# M652X.net
KiCad netlist of a schematic drawn in EAGLE
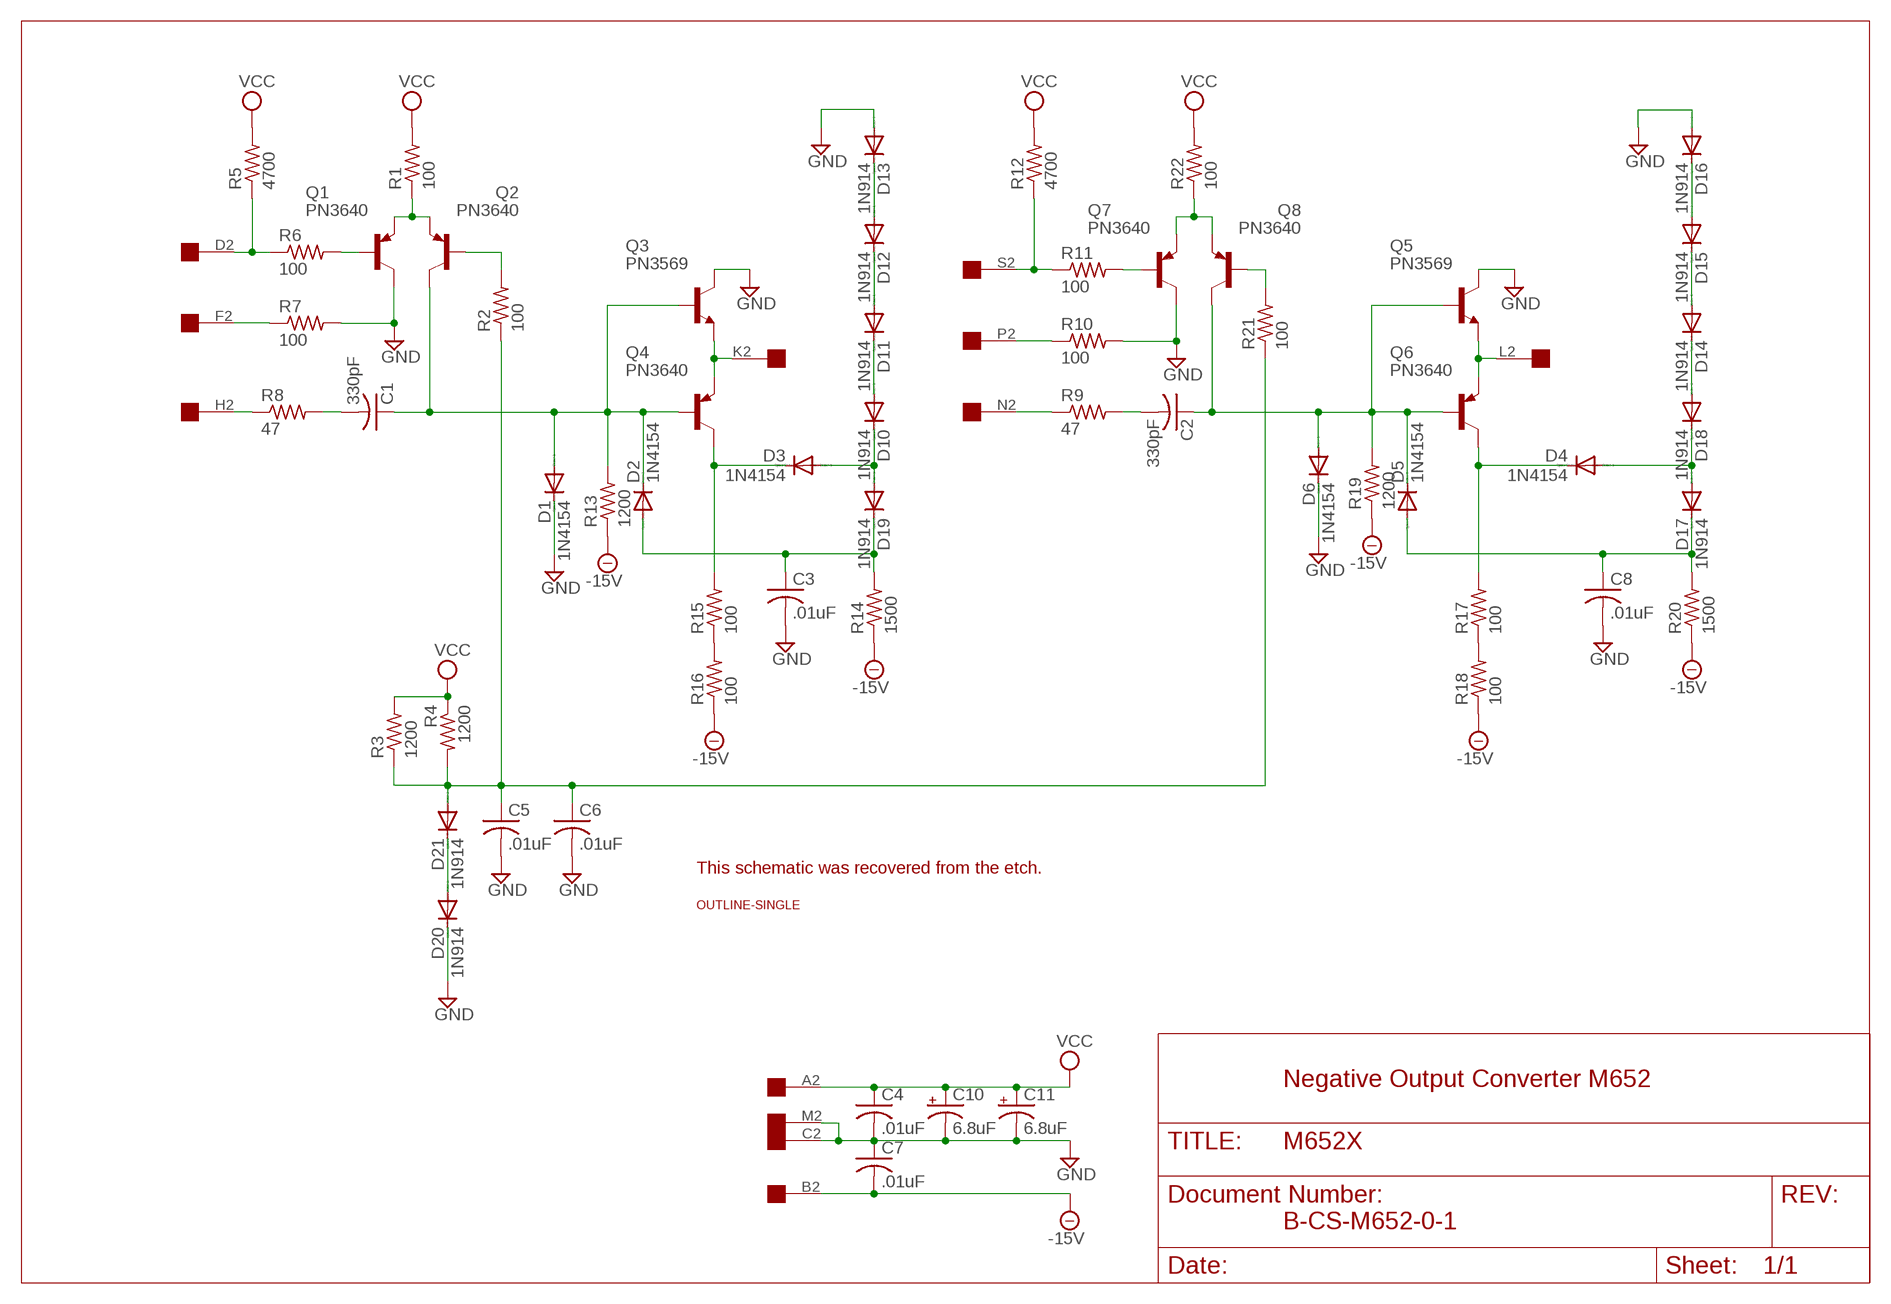
[diagram p0: schematic, sheet 1]

(export (version "E")
  (design (tool "Eeschema 10.0.6"))
  (components
    (comp (ref "C1")
      (value "330pF")
      (footprint "eagle-import:C150-054X183")
      (libsource (lib "eagle-import") (part "C-US150-054X183"))
    )
    (comp (ref "C2")
      (value "330pF")
      (footprint "eagle-import:C150-054X183")
      (libsource (lib "eagle-import") (part "C-US150-054X183"))
    )
    (comp (ref "C3")
      (value ".01uF")
      (footprint "eagle-import:C050-025X075")
      (libsource (lib "eagle-import") (part "C-US050-025X075"))
    )
    (comp (ref "C4")
      (value ".01uF")
      (footprint "eagle-import:C050-025X075")
      (libsource (lib "eagle-import") (part "C-US050-025X075"))
    )
    (comp (ref "C5")
      (value ".01uF")
      (footprint "eagle-import:C050-025X075")
      (libsource (lib "eagle-import") (part "C-US050-025X075"))
    )
    (comp (ref "C6")
      (value ".01uF")
      (footprint "eagle-import:C050-025X075")
      (libsource (lib "eagle-import") (part "C-US050-025X075"))
    )
    (comp (ref "C7")
      (value ".01uF")
      (footprint "eagle-import:C050-025X075")
      (libsource (lib "eagle-import") (part "C-US050-025X075"))
    )
    (comp (ref "C8")
      (value ".01uF")
      (footprint "eagle-import:C050-025X075")
      (libsource (lib "eagle-import") (part "C-US050-025X075"))
    )
    (comp (ref "C10")
      (value "6.8uF")
      (footprint "eagle-import:E12-4")
      (libsource (lib "eagle-import") (part "CPOL-USE12-4AXIAL"))
    )
    (comp (ref "C11")
      (value "6.8uF")
      (footprint "eagle-import:E12-4")
      (libsource (lib "eagle-import") (part "CPOL-USE12-4AXIAL"))
    )
    (comp (ref "D1")
      (value "1N4154")
      (footprint "eagle-import:DO35-10")
      (libsource (lib "eagle-import") (part "1N4148DO35-10"))
    )
    (comp (ref "D2")
      (value "1N4154")
      (footprint "eagle-import:DO35-10")
      (libsource (lib "eagle-import") (part "1N4148DO35-10"))
    )
    (comp (ref "D3")
      (value "1N4154")
      (footprint "eagle-import:DO35-10")
      (libsource (lib "eagle-import") (part "1N4148DO35-10"))
    )
    (comp (ref "D4")
      (value "1N4154")
      (footprint "eagle-import:DO35-10")
      (libsource (lib "eagle-import") (part "1N4148DO35-10"))
    )
    (comp (ref "D5")
      (value "1N4154")
      (footprint "eagle-import:DO35-10")
      (libsource (lib "eagle-import") (part "1N4148DO35-10"))
    )
    (comp (ref "D6")
      (value "1N4154")
      (footprint "eagle-import:DO35-10")
      (libsource (lib "eagle-import") (part "1N4148DO35-10"))
    )
    (comp (ref "D10")
      (value "1N914")
      (footprint "eagle-import:DO35-10")
      (libsource (lib "eagle-import") (part "1N4148DO35-10"))
    )
    (comp (ref "D11")
      (value "1N914")
      (footprint "eagle-import:DO35-10")
      (libsource (lib "eagle-import") (part "1N4148DO35-10"))
    )
    (comp (ref "D12")
      (value "1N914")
      (footprint "eagle-import:DO35-10")
      (libsource (lib "eagle-import") (part "1N4148DO35-10"))
    )
    (comp (ref "D13")
      (value "1N914")
      (footprint "eagle-import:DO35-10")
      (libsource (lib "eagle-import") (part "1N4148DO35-10"))
    )
    (comp (ref "D14")
      (value "1N914")
      (footprint "eagle-import:DO35-10")
      (libsource (lib "eagle-import") (part "1N4148DO35-10"))
    )
    (comp (ref "D15")
      (value "1N914")
      (footprint "eagle-import:DO35-10")
      (libsource (lib "eagle-import") (part "1N4148DO35-10"))
    )
    (comp (ref "D16")
      (value "1N914")
      (footprint "eagle-import:DO35-10")
      (libsource (lib "eagle-import") (part "1N4148DO35-10"))
    )
    (comp (ref "D17")
      (value "1N914")
      (footprint "eagle-import:DO35-10")
      (libsource (lib "eagle-import") (part "1N4148DO35-10"))
    )
    (comp (ref "D18")
      (value "1N914")
      (footprint "eagle-import:DO35-10")
      (libsource (lib "eagle-import") (part "1N4148DO35-10"))
    )
    (comp (ref "D19")
      (value "1N914")
      (footprint "eagle-import:DO35-10")
      (libsource (lib "eagle-import") (part "1N4148DO35-10"))
    )
    (comp (ref "D20")
      (value "1N914")
      (footprint "eagle-import:DO35-10")
      (libsource (lib "eagle-import") (part "1N4148DO35-10"))
    )
    (comp (ref "D21")
      (value "1N914")
      (footprint "eagle-import:DO35-10")
      (libsource (lib "eagle-import") (part "1N4148DO35-10"))
    )
    (comp (ref "Q1")
      (value "PN3640")
      (footprint "eagle-import:TO39")
      (libsource (lib "eagle-import") (part "2N5415"))
    )
    (comp (ref "Q2")
      (value "PN3640")
      (footprint "eagle-import:TO39")
      (libsource (lib "eagle-import") (part "2N5415"))
    )
    (comp (ref "Q3")
      (value "PN3569")
      (footprint "eagle-import:TO5")
      (libsource (lib "eagle-import") (part "2N2219"))
    )
    (comp (ref "Q4")
      (value "PN3640")
      (footprint "eagle-import:TO39")
      (libsource (lib "eagle-import") (part "2N5415"))
    )
    (comp (ref "Q5")
      (value "PN3569")
      (footprint "eagle-import:TO5")
      (libsource (lib "eagle-import") (part "2N2219"))
    )
    (comp (ref "Q6")
      (value "PN3640")
      (footprint "eagle-import:TO39")
      (libsource (lib "eagle-import") (part "2N5415"))
    )
    (comp (ref "Q7")
      (value "PN3640")
      (footprint "eagle-import:TO39")
      (libsource (lib "eagle-import") (part "2N5415"))
    )
    (comp (ref "Q8")
      (value "PN3640")
      (footprint "eagle-import:TO39")
      (libsource (lib "eagle-import") (part "2N5415"))
    )
    (comp (ref "R1")
      (value "100")
      (footprint "eagle-import:0207_10")
      (libsource (lib "eagle-import") (part "R-US_0207/10"))
    )
    (comp (ref "R2")
      (value "100")
      (footprint "eagle-import:0207_10")
      (libsource (lib "eagle-import") (part "R-US_0207/10"))
    )
    (comp (ref "R3")
      (value "1200")
      (footprint "eagle-import:0207_10")
      (libsource (lib "eagle-import") (part "R-US_0207/10"))
    )
    (comp (ref "R4")
      (value "1200")
      (footprint "eagle-import:0207_10")
      (libsource (lib "eagle-import") (part "R-US_0207/10"))
    )
    (comp (ref "R5")
      (value "4700")
      (footprint "eagle-import:0207_10")
      (libsource (lib "eagle-import") (part "R-US_0207/10"))
    )
    (comp (ref "R6")
      (value "100")
      (footprint "eagle-import:0207_10")
      (libsource (lib "eagle-import") (part "R-US_0207/10"))
    )
    (comp (ref "R7")
      (value "100")
      (footprint "eagle-import:0207_10")
      (libsource (lib "eagle-import") (part "R-US_0207/10"))
    )
    (comp (ref "R8")
      (value "47")
      (footprint "eagle-import:0207_10")
      (libsource (lib "eagle-import") (part "R-US_0207/10"))
    )
    (comp (ref "R9")
      (value "47")
      (footprint "eagle-import:0207_10")
      (libsource (lib "eagle-import") (part "R-US_0207/10"))
    )
    (comp (ref "R10")
      (value "100")
      (footprint "eagle-import:0207_10")
      (libsource (lib "eagle-import") (part "R-US_0207/10"))
    )
    (comp (ref "R11")
      (value "100")
      (footprint "eagle-import:0207_10")
      (libsource (lib "eagle-import") (part "R-US_0207/10"))
    )
    (comp (ref "R12")
      (value "4700")
      (footprint "eagle-import:0207_10")
      (libsource (lib "eagle-import") (part "R-US_0207/10"))
    )
    (comp (ref "R13")
      (value "1200")
      (footprint "eagle-import:0207_10")
      (libsource (lib "eagle-import") (part "R-US_0207/10"))
    )
    (comp (ref "R14")
      (value "1500")
      (footprint "eagle-import:0207_10")
      (libsource (lib "eagle-import") (part "R-US_0207/10"))
    )
    (comp (ref "R15")
      (value "100")
      (footprint "eagle-import:0207_10")
      (libsource (lib "eagle-import") (part "R-US_0207/10"))
    )
    (comp (ref "R16")
      (value "100")
      (footprint "eagle-import:0207_10")
      (libsource (lib "eagle-import") (part "R-US_0207/10"))
    )
    (comp (ref "R17")
      (value "100")
      (footprint "eagle-import:0207_10")
      (libsource (lib "eagle-import") (part "R-US_0207/10"))
    )
    (comp (ref "R18")
      (value "100")
      (footprint "eagle-import:0207_10")
      (libsource (lib "eagle-import") (part "R-US_0207/10"))
    )
    (comp (ref "R19")
      (value "1200")
      (footprint "eagle-import:0207_10")
      (libsource (lib "eagle-import") (part "R-US_0207/10"))
    )
    (comp (ref "R20")
      (value "1500")
      (footprint "eagle-import:0207_10")
      (libsource (lib "eagle-import") (part "R-US_0207/10"))
    )
    (comp (ref "R21")
      (value "100")
      (footprint "eagle-import:0207_10")
      (libsource (lib "eagle-import") (part "R-US_0207/10"))
    )
    (comp (ref "R22")
      (value "100")
      (footprint "eagle-import:0207_10")
      (libsource (lib "eagle-import") (part "R-US_0207/10"))
    )
    (comp (ref "U$1")
      (value "OUTLINE-SINGLE")
      (footprint "eagle-import:SINGLE")
      (libsource (lib "eagle-import") (part "OUTLINE-SINGLE"))
    )
    (comp (ref "U$3")
      (value "EDGE-1")
      (footprint "eagle-import:EDGE-CON1")
      (libsource (lib "eagle-import") (part "EDGE-1"))
    )
  )
  (nets
    (net (code "1") (name "-15V") (class "Default")
      (node (ref "C7") (pin "2") (pinfunction "2_2") (pintype "passive"))
      (node (ref "R13") (pin "1") (pinfunction "1_1") (pintype "passive"))
      (node (ref "R14") (pin "1") (pinfunction "1_1") (pintype "passive"))
      (node (ref "R16") (pin "1") (pinfunction "1_1") (pintype "passive"))
      (node (ref "R18") (pin "1") (pinfunction "1_1") (pintype "passive"))
      (node (ref "R19") (pin "1") (pinfunction "1_1") (pintype "passive"))
      (node (ref "R20") (pin "1") (pinfunction "1_1") (pintype "passive"))
      (node (ref "U$3") (pin "B2") (pinfunction "1_B2") (pintype "bidirectional"))
    )
    (net (code "2") (name "GND") (class "Default")
      (node (ref "C10") (pin "-") (pinfunction "-_-") (pintype "passive"))
      (node (ref "C11") (pin "-") (pinfunction "-_-") (pintype "passive"))
      (node (ref "C3") (pin "2") (pinfunction "2_2") (pintype "passive"))
      (node (ref "C4") (pin "2") (pinfunction "2_2") (pintype "passive"))
      (node (ref "C5") (pin "2") (pinfunction "2_2") (pintype "passive"))
      (node (ref "C6") (pin "2") (pinfunction "2_2") (pintype "passive"))
      (node (ref "C7") (pin "1") (pinfunction "1_1") (pintype "passive"))
      (node (ref "C8") (pin "2") (pinfunction "2_2") (pintype "passive"))
      (node (ref "D1") (pin "C") (pinfunction "C_C") (pintype "passive"))
      (node (ref "D13") (pin "A") (pinfunction "A_A") (pintype "passive"))
      (node (ref "D16") (pin "A") (pinfunction "A_A") (pintype "passive"))
      (node (ref "D20") (pin "C") (pinfunction "C_C") (pintype "passive"))
      (node (ref "D6") (pin "C") (pinfunction "C_C") (pintype "passive"))
      (node (ref "Q1") (pin "3") (pinfunction "C_3") (pintype "passive"))
      (node (ref "Q3") (pin "3") (pinfunction "C_3") (pintype "passive"))
      (node (ref "Q5") (pin "3") (pinfunction "C_3") (pintype "passive"))
      (node (ref "Q7") (pin "3") (pinfunction "C_3") (pintype "passive"))
      (node (ref "R10") (pin "2") (pinfunction "2_2") (pintype "passive"))
      (node (ref "R7") (pin "2") (pinfunction "2_2") (pintype "passive"))
      (node (ref "U$3") (pin "C2") (pinfunction "1_C2") (pintype "bidirectional"))
      (node (ref "U$3") (pin "M2") (pinfunction "1_M2") (pintype "bidirectional"))
    )
    (net (code "3") (name "Net-(C1-Pad2)") (class "Default")
      (node (ref "C1") (pin "2") (pinfunction "2_2") (pintype "passive"))
      (node (ref "R8") (pin "2") (pinfunction "2_2") (pintype "passive"))
    )
    (net (code "4") (name "Net-(C2-Pad2)") (class "Default")
      (node (ref "C2") (pin "2") (pinfunction "2_2") (pintype "passive"))
      (node (ref "R9") (pin "2") (pinfunction "2_2") (pintype "passive"))
    )
    (net (code "5") (name "Net-(C3-Pad1)") (class "Default")
      (node (ref "C3") (pin "1") (pinfunction "1_1") (pintype "passive"))
      (node (ref "D19") (pin "C") (pinfunction "C_C") (pintype "passive"))
      (node (ref "D2") (pin "A") (pinfunction "A_A") (pintype "passive"))
      (node (ref "R14") (pin "2") (pinfunction "2_2") (pintype "passive"))
    )
    (net (code "6") (name "Net-(C5-Pad1)") (class "Default")
      (node (ref "C5") (pin "1") (pinfunction "1_1") (pintype "passive"))
      (node (ref "C6") (pin "1") (pinfunction "1_1") (pintype "passive"))
      (node (ref "D21") (pin "A") (pinfunction "A_A") (pintype "passive"))
      (node (ref "R2") (pin "1") (pinfunction "1_1") (pintype "passive"))
      (node (ref "R21") (pin "1") (pinfunction "1_1") (pintype "passive"))
      (node (ref "R3") (pin "1") (pinfunction "1_1") (pintype "passive"))
      (node (ref "R4") (pin "2") (pinfunction "2_2") (pintype "passive"))
    )
    (net (code "7") (name "Net-(C8-Pad1)") (class "Default")
      (node (ref "C8") (pin "1") (pinfunction "1_1") (pintype "passive"))
      (node (ref "D17") (pin "C") (pinfunction "C_C") (pintype "passive"))
      (node (ref "D5") (pin "A") (pinfunction "A_A") (pintype "passive"))
      (node (ref "R20") (pin "2") (pinfunction "2_2") (pintype "passive"))
    )
    (net (code "8") (name "Net-(D10-PadA)") (class "Default")
      (node (ref "D10") (pin "A") (pinfunction "A_A") (pintype "passive"))
      (node (ref "D11") (pin "C") (pinfunction "C_C") (pintype "passive"))
    )
    (net (code "9") (name "Net-(D10-PadC)") (class "Default")
      (node (ref "D10") (pin "C") (pinfunction "C_C") (pintype "passive"))
      (node (ref "D19") (pin "A") (pinfunction "A_A") (pintype "passive"))
      (node (ref "D3") (pin "A") (pinfunction "A_A") (pintype "passive"))
    )
    (net (code "10") (name "Net-(D11-PadA)") (class "Default")
      (node (ref "D11") (pin "A") (pinfunction "A_A") (pintype "passive"))
      (node (ref "D12") (pin "C") (pinfunction "C_C") (pintype "passive"))
    )
    (net (code "11") (name "Net-(D12-PadA)") (class "Default")
      (node (ref "D12") (pin "A") (pinfunction "A_A") (pintype "passive"))
      (node (ref "D13") (pin "C") (pinfunction "C_C") (pintype "passive"))
    )
    (net (code "12") (name "Net-(D14-PadA)") (class "Default")
      (node (ref "D14") (pin "A") (pinfunction "A_A") (pintype "passive"))
      (node (ref "D15") (pin "C") (pinfunction "C_C") (pintype "passive"))
    )
    (net (code "13") (name "Net-(D14-PadC)") (class "Default")
      (node (ref "D14") (pin "C") (pinfunction "C_C") (pintype "passive"))
      (node (ref "D18") (pin "A") (pinfunction "A_A") (pintype "passive"))
    )
    (net (code "14") (name "Net-(D15-PadA)") (class "Default")
      (node (ref "D15") (pin "A") (pinfunction "A_A") (pintype "passive"))
      (node (ref "D16") (pin "C") (pinfunction "C_C") (pintype "passive"))
    )
    (net (code "15") (name "Net-(D17-PadA)") (class "Default")
      (node (ref "D17") (pin "A") (pinfunction "A_A") (pintype "passive"))
      (node (ref "D18") (pin "C") (pinfunction "C_C") (pintype "passive"))
      (node (ref "D4") (pin "A") (pinfunction "A_A") (pintype "passive"))
    )
    (net (code "16") (name "Net-(D20-PadA)") (class "Default")
      (node (ref "D20") (pin "A") (pinfunction "A_A") (pintype "passive"))
      (node (ref "D21") (pin "C") (pinfunction "C_C") (pintype "passive"))
    )
    (net (code "17") (name "Net-(Q1-B)") (class "Default")
      (node (ref "Q1") (pin "2") (pinfunction "B_2") (pintype "passive"))
      (node (ref "R6") (pin "2") (pinfunction "2_2") (pintype "passive"))
    )
    (net (code "18") (name "Net-(Q1-E)") (class "Default")
      (node (ref "Q1") (pin "1") (pinfunction "E_1") (pintype "passive"))
      (node (ref "Q2") (pin "1") (pinfunction "E_1") (pintype "passive"))
      (node (ref "R1") (pin "1") (pinfunction "1_1") (pintype "passive"))
    )
    (net (code "19") (name "Net-(Q2-B)") (class "Default")
      (node (ref "Q2") (pin "2") (pinfunction "B_2") (pintype "passive"))
      (node (ref "R2") (pin "2") (pinfunction "2_2") (pintype "passive"))
    )
    (net (code "20") (name "Net-(Q2-C)") (class "Default")
      (node (ref "C1") (pin "1") (pinfunction "1_1") (pintype "passive"))
      (node (ref "D1") (pin "A") (pinfunction "A_A") (pintype "passive"))
      (node (ref "D2") (pin "C") (pinfunction "C_C") (pintype "passive"))
      (node (ref "Q2") (pin "3") (pinfunction "C_3") (pintype "passive"))
      (node (ref "Q3") (pin "2") (pinfunction "B_2") (pintype "passive"))
      (node (ref "Q4") (pin "2") (pinfunction "B_2") (pintype "passive"))
      (node (ref "R13") (pin "2") (pinfunction "2_2") (pintype "passive"))
    )
    (net (code "21") (name "Net-(Q3-E)") (class "Default")
      (node (ref "Q3") (pin "1") (pinfunction "E_1") (pintype "passive"))
      (node (ref "Q4") (pin "1") (pinfunction "E_1") (pintype "passive"))
      (node (ref "U$3") (pin "K2") (pinfunction "1_K2") (pintype "bidirectional"))
    )
    (net (code "22") (name "Net-(Q4-C)") (class "Default")
      (node (ref "D3") (pin "C") (pinfunction "C_C") (pintype "passive"))
      (node (ref "Q4") (pin "3") (pinfunction "C_3") (pintype "passive"))
      (node (ref "R15") (pin "2") (pinfunction "2_2") (pintype "passive"))
    )
    (net (code "23") (name "Net-(Q5-B)") (class "Default")
      (node (ref "C2") (pin "1") (pinfunction "1_1") (pintype "passive"))
      (node (ref "D5") (pin "C") (pinfunction "C_C") (pintype "passive"))
      (node (ref "D6") (pin "A") (pinfunction "A_A") (pintype "passive"))
      (node (ref "Q5") (pin "2") (pinfunction "B_2") (pintype "passive"))
      (node (ref "Q6") (pin "2") (pinfunction "B_2") (pintype "passive"))
      (node (ref "Q8") (pin "3") (pinfunction "C_3") (pintype "passive"))
      (node (ref "R19") (pin "2") (pinfunction "2_2") (pintype "passive"))
    )
    (net (code "24") (name "Net-(Q5-E)") (class "Default")
      (node (ref "Q5") (pin "1") (pinfunction "E_1") (pintype "passive"))
      (node (ref "Q6") (pin "1") (pinfunction "E_1") (pintype "passive"))
      (node (ref "U$3") (pin "L2") (pinfunction "1_L2") (pintype "bidirectional"))
    )
    (net (code "25") (name "Net-(Q6-C)") (class "Default")
      (node (ref "D4") (pin "C") (pinfunction "C_C") (pintype "passive"))
      (node (ref "Q6") (pin "3") (pinfunction "C_3") (pintype "passive"))
      (node (ref "R17") (pin "2") (pinfunction "2_2") (pintype "passive"))
    )
    (net (code "26") (name "Net-(Q7-B)") (class "Default")
      (node (ref "Q7") (pin "2") (pinfunction "B_2") (pintype "passive"))
      (node (ref "R11") (pin "2") (pinfunction "2_2") (pintype "passive"))
    )
    (net (code "27") (name "Net-(Q7-E)") (class "Default")
      (node (ref "Q7") (pin "1") (pinfunction "E_1") (pintype "passive"))
      (node (ref "Q8") (pin "1") (pinfunction "E_1") (pintype "passive"))
      (node (ref "R22") (pin "1") (pinfunction "1_1") (pintype "passive"))
    )
    (net (code "28") (name "Net-(Q8-B)") (class "Default")
      (node (ref "Q8") (pin "2") (pinfunction "B_2") (pintype "passive"))
      (node (ref "R21") (pin "2") (pinfunction "2_2") (pintype "passive"))
    )
    (net (code "29") (name "Net-(R15-Pad1)") (class "Default")
      (node (ref "R15") (pin "1") (pinfunction "1_1") (pintype "passive"))
      (node (ref "R16") (pin "2") (pinfunction "2_2") (pintype "passive"))
    )
    (net (code "30") (name "Net-(R17-Pad1)") (class "Default")
      (node (ref "R17") (pin "1") (pinfunction "1_1") (pintype "passive"))
      (node (ref "R18") (pin "2") (pinfunction "2_2") (pintype "passive"))
    )
    (net (code "31") (name "Net-(U$3D-1)") (class "Default")
      (node (ref "R5") (pin "1") (pinfunction "1_1") (pintype "passive"))
      (node (ref "R6") (pin "1") (pinfunction "1_1") (pintype "passive"))
      (node (ref "U$3") (pin "D2") (pinfunction "1_D2") (pintype "bidirectional"))
    )
    (net (code "32") (name "Net-(U$3F-1)") (class "Default")
      (node (ref "R7") (pin "1") (pinfunction "1_1") (pintype "passive"))
      (node (ref "U$3") (pin "F2") (pinfunction "1_F2") (pintype "bidirectional"))
    )
    (net (code "33") (name "Net-(U$3G-1)") (class "Default")
      (node (ref "R8") (pin "1") (pinfunction "1_1") (pintype "passive"))
      (node (ref "U$3") (pin "H2") (pinfunction "1_H2") (pintype "bidirectional"))
    )
    (net (code "34") (name "Net-(U$3L-1)") (class "Default")
      (node (ref "R9") (pin "1") (pinfunction "1_1") (pintype "passive"))
      (node (ref "U$3") (pin "N2") (pinfunction "1_N2") (pintype "bidirectional"))
    )
    (net (code "35") (name "Net-(U$3M-1)") (class "Default")
      (node (ref "R10") (pin "1") (pinfunction "1_1") (pintype "passive"))
      (node (ref "U$3") (pin "P2") (pinfunction "1_P2") (pintype "bidirectional"))
    )
    (net (code "36") (name "Net-(U$3O-1)") (class "Default")
      (node (ref "R11") (pin "1") (pinfunction "1_1") (pintype "passive"))
      (node (ref "R12") (pin "1") (pinfunction "1_1") (pintype "passive"))
      (node (ref "U$3") (pin "S2") (pinfunction "1_S2") (pintype "bidirectional"))
    )
    (net (code "37") (name "VCC") (class "Default")
      (node (ref "C10") (pin "+") (pinfunction "+_+") (pintype "passive"))
      (node (ref "C11") (pin "+") (pinfunction "+_+") (pintype "passive"))
      (node (ref "C4") (pin "1") (pinfunction "1_1") (pintype "passive"))
      (node (ref "R1") (pin "2") (pinfunction "2_2") (pintype "passive"))
      (node (ref "R12") (pin "2") (pinfunction "2_2") (pintype "passive"))
      (node (ref "R22") (pin "2") (pinfunction "2_2") (pintype "passive"))
      (node (ref "R3") (pin "2") (pinfunction "2_2") (pintype "passive"))
      (node (ref "R4") (pin "1") (pinfunction "1_1") (pintype "passive"))
      (node (ref "R5") (pin "2") (pinfunction "2_2") (pintype "passive"))
      (node (ref "U$3") (pin "A2") (pinfunction "1_A2") (pintype "bidirectional"))
    )
  )
)
